# power-v5v5.net
KiCad netlist of a schematic drawn in Altium Designer
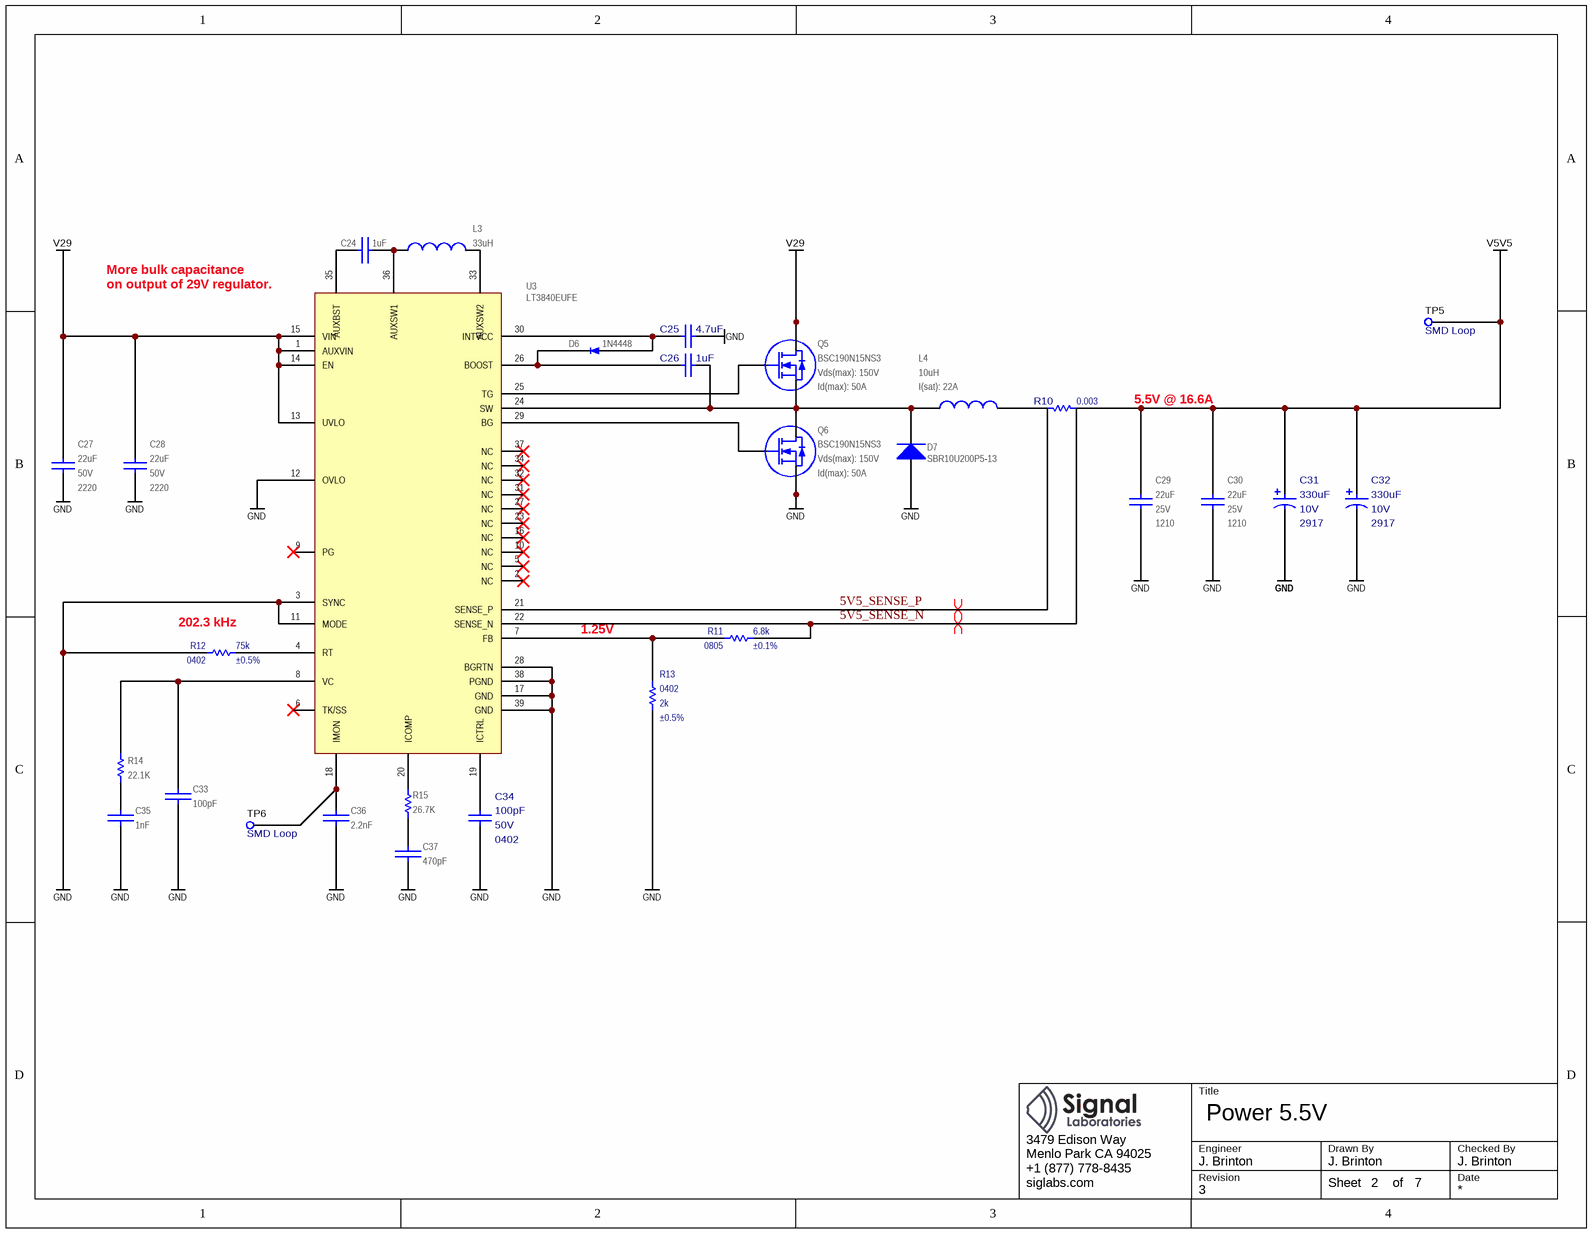
[diagram p0: power-v5v5.SchDoc]

(export (version "E")
  (design (tool "Eeschema 10.0.6"))
  (components
    (comp (ref "C24")
      (value "1uF")
      (footprint "CAPC100X50X55L25N")
      (description "Ceramic Capacitor 1uF ±10% 10V X5R 0402")
      (fields (field (name "MANUFACTURER") "Murata") (field (name "TOLERANCE") "±10%"))
      (libsource (lib "*") (part "CAP"))
    )
    (comp (ref "C25")
      (value "4.7uF")
      (footprint "CAPC160X80X90L20NA")
      (description "Ceramic Capacitor 4.7uF ±10% 25V X5R 0603")
      (fields (field (name "MANUFACTURER") "Samsung") (field (name "TOLERANCE") "±10%"))
      (libsource (lib "capacitors") (part "CAP"))
    )
    (comp (ref "C26")
      (value "1uF")
      (footprint "CAPC100X50X55L25N")
      (description "Ceramic Capacitor 1uF ±10% 10V X5R 0402")
      (fields (field (name "MANUFACTURER") "Murata") (field (name "TOLERANCE") "±10%"))
      (libsource (lib "capacitors") (part "CAP"))
    )
    (comp (ref "C27")
      (value "22uF")
      (footprint "CAPC600X500X500L160N")
      (description "Ceramic Capacitor 22uF ±20% 50V X7S Stacked")
      (fields
        (field (name "MANUFACTURER") "TDK")
        (field (name "TOLERANCE") "±20%")
        (field (name "VOLTAGE") "50V")
        (field (name "PACKAGE") "2220")
      )
      (libsource (lib "generic") (part "CAP"))
    )
    (comp (ref "C28")
      (value "22uF")
      (footprint "CAPC600X500X500L160N")
      (description "Ceramic Capacitor 22uF ±20% 50V X7S Stacked")
      (fields
        (field (name "MANUFACTURER") "TDK")
        (field (name "TOLERANCE") "±20%")
        (field (name "VOLTAGE") "50V")
        (field (name "PACKAGE") "2220")
      )
      (libsource (lib "generic") (part "CAP"))
    )
    (comp (ref "C29")
      (value "22uF")
      (footprint "CAPC320X250X270L50N")
      (description "Ceramic Capacitor 22uF ±10% 25V X7R 1210")
      (fields
        (field (name "MANUFACTURER") "Murata")
        (field (name "TOLERANCE") "±10%")
        (field (name "VOLTAGE") "25V")
        (field (name "PACKAGE") "1210")
      )
      (libsource (lib "generic") (part "CAP"))
    )
    (comp (ref "C30")
      (value "22uF")
      (footprint "CAPC320X250X270L50N")
      (description "Ceramic Capacitor 22uF ±10% 25V X7R 1210")
      (fields
        (field (name "MANUFACTURER") "Murata")
        (field (name "TOLERANCE") "±10%")
        (field (name "VOLTAGE") "25V")
        (field (name "PACKAGE") "1210")
      )
      (libsource (lib "generic") (part "CAP"))
    )
    (comp (ref "C31")
      (value "330uF")
      (footprint "CAPPM730X435X310L135X240N")
      (description "Tantalum Capacitor 330uF ±10% 10V 2917")
      (fields
        (field (name "MANUFACTURER") "AVX")
        (field (name "TOLERANCE") "±10%")
        (field (name "PACKAGE") "2917")
        (field (name "VOLTAGE") "10V")
      )
      (libsource (lib "avx") (part "CAP_POL"))
    )
    (comp (ref "C32")
      (value "330uF")
      (footprint "CAPPM730X435X310L135X240N")
      (description "Tantalum Capacitor 330uF ±10% 10V 2917")
      (fields
        (field (name "MANUFACTURER") "AVX")
        (field (name "TOLERANCE") "±10%")
        (field (name "PACKAGE") "2917")
        (field (name "VOLTAGE") "10V")
      )
      (libsource (lib "avx") (part "CAP_POL"))
    )
    (comp (ref "C33")
      (value "100pF")
      (footprint "CAPC100X50X55L25N")
      (description "Ceramic Capacitor 100pF ±1% 50V NP0 0402")
      (fields (field (name "MANUFACTURER") "Murata") (field (name "VOLTAGE") "50V"))
      (libsource (lib "*") (part "CAP"))
    )
    (comp (ref "C34")
      (value "100pF")
      (footprint "generic:CAPC100X50X55L25N")
      (description "Ceramic Capacitor 100pF ±10% 50V C0G 0402")
      (fields
        (field (name "MANUFACTURER") "Vishay")
        (field (name "TOLERANCE") "±10%")
        (field (name "PACKAGE") "0402")
        (field (name "VOLTAGE") "50V")
      )
      (libsource (lib "capacitors") (part "CAP"))
    )
    (comp (ref "C35")
      (value "1nF")
      (footprint "CAPC100X50X55L25N")
      (description "Ceramic Capacitor 1nF ±5% 50V NP0 0402")
      (fields (field (name "MANUFACTURER") "Murata") (field (name "VOLTAGE") "50V"))
      (libsource (lib "*") (part "CAP"))
    )
    (comp (ref "C36")
      (value "2.2nF")
      (footprint "CAPC100X50X55L25N")
      (description "Ceramic Capacitor 2.2nF ±5% 25V NP0 0402")
      (fields (field (name "MANUFACTURER") "Kemet") (field (name "TOLERANCE") "±5%"))
      (libsource (lib "*") (part "CAP"))
    )
    (comp (ref "C37")
      (value "470pF")
      (footprint "CAPC100X50X55L25N")
      (description "Ceramic Capacitor 470pF ±5% 50V X7R 0402")
      (fields (field (name "MANUFACTURER") "Murata") (field (name "VOLTAGE") "50V"))
      (libsource (lib "*") (part "CAP"))
    )
    (comp (ref "D6")
      (value "1N4448HWS-7-F")
      (footprint "diodes_inc:SOD323")
      (description "Schottky Diode 80V 250mA SOD323")
      (fields (field (name "MANUFACTURER") "Diodes Inc") (field (name "ALTERNATIVE P/N") "1N4448"))
      (libsource (lib "diodes_inc") (part "1N4448HWS-7-F"))
    )
    (comp (ref "D7")
      (value "SBR10U200P5-13")
      (footprint "DIODES_POWERDI5")
      (description "Schottky Diode 200V 10A SMD")
      (fields (field (name "MANUFACTURER") "Diodes Inc"))
      (libsource (lib "diodes_inc") (part "PDS5100H"))
    )
    (comp (ref "L3")
      (value "33uH")
      (footprint "coilcraft:ME3220")
      (description "Inductor 33uH ±10% 500mA SMD")
      (fields (field (name "MANUFACTURER") "Coilcraft") (field (name "TOLERANCE") "±10%"))
      (libsource (lib "CamBoard_Pico_70.19K") (part "COIL"))
    )
    (comp (ref "L4")
      (value "10uH")
      (footprint "HCM1A1707")
      (description "Inductor 10uH, 22A(sat), SMD")
      (fields
        (field (name "MANUFACTURER") "Pulse Electronics Power")
        (field (name "I(SAT)") "22A")
        (field (name "Comment") "PA4344.103ANLT")
      )
      (libsource (lib "CamBoard_Pico_70.19K") (part "COIL"))
    )
    (comp (ref "Q5")
      (value "BSC190N15NS3")
      (footprint "TDSON-8")
      (description "MOSFET N-Channel Enhancement Mode")
      (fields
        (field (name "MANUFACTURER") "Infineon")
        (field (name "VDS(MAX)") "150V")
        (field (name "ID(MAX)") "50A")
      )
      (libsource (lib "infinion") (part "BSC190N15NS3"))
    )
    (comp (ref "Q6")
      (value "BSC190N15NS3")
      (footprint "TDSON-8")
      (description "MOSFET N-Channel Enhancement Mode")
      (fields
        (field (name "MANUFACTURER") "Infineon")
        (field (name "VDS(MAX)") "150V")
        (field (name "ID(MAX)") "50A")
      )
      (libsource (lib "infinion") (part "BSC190N15NS3"))
    )
    (comp (ref "R10")
      (value "0.003")
      (footprint "susumu:KRL3216T4")
      (description "Current Sense Resistor 3 mOhms +/-1% SMD 4-Terminal")
      (fields (field (name "TOLERANCE") "±1%") (field (name "MANUFACTURER") "Susumu"))
      (libsource (lib "susumu") (part "KRL3216T4A-M-R009-F"))
    )
    (comp (ref "R11")
      (value "6.8k")
      (footprint "RESC2012X70N")
      (description "Thin Film Resistor 6.8k +/-0.1% SMD 0805")
      (fields
        (field (name "TOLERANCE") "±0.1%")
        (field (name "MANUFACTURER") "Susumu")
        (field (name "PACKAGE") "0805")
        (field (name "Comment") "RG2012P-682-B-T5")
      )
      (libsource (lib "generic") (part "RES"))
    )
    (comp (ref "R12")
      (value "75k")
      (footprint "RESC1005X40N")
      (description "Thin Film Resistor 75k +/-0.5% SMD 0402")
      (fields
        (field (name "TOLERANCE") "±0.5%")
        (field (name "MANUFACTURER") "Susumu")
        (field (name "PACKAGE") "0402")
        (field (name "Comment") "RR0510P-753-D")
      )
      (libsource (lib "generic") (part "RES"))
    )
    (comp (ref "R13")
      (value "2k")
      (footprint "RESC1005X40N")
      (description "Thin Film Resistor 2k +/-0.5% SMD 0402")
      (fields
        (field (name "TOLERANCE") "±0.5%")
        (field (name "MANUFACTURER") "Susumu")
        (field (name "PACKAGE") "0402")
        (field (name "Comment") "RR0510P-202-D")
      )
      (libsource (lib "generic") (part "RES"))
    )
    (comp (ref "R14")
      (value "22.1K")
      (footprint "generic:RESC1005X40N")
      (description "Thick Film Resistor 22.1k ±1% 0402")
      (fields (field (name "MANUFACTURER") "Panasonic") (field (name "TOLERANCE") "±1%"))
      (libsource (lib "Graviton") (part "RES 0402"))
    )
    (comp (ref "R15")
      (value "26.7K")
      (footprint "generic:RESC1005X40N")
      (description "Thick Film Resistor 26.7k ±1% 0402")
      (fields (field (name "MANUFACTURER") "Panasonic") (field (name "TOLERANCE") "±1%"))
      (libsource (lib "Graviton") (part "RES 0402"))
    )
    (comp (ref "TP5")
      (value "5015")
      (footprint "keystone:5015")
      (description "Test Point SMD")
      (fields (field (name "MANUFACTURER") "Keystone") (field (name "NOTES") "SMD Loop"))
      (libsource (lib "generic") (part "TEST_POINT_SMD_50"))
    )
    (comp (ref "TP6")
      (value "5015")
      (footprint "keystone:5015")
      (description "Test Point SMD")
      (fields (field (name "MANUFACTURER") "Keystone") (field (name "NOTES") "SMD Loop"))
      (libsource (lib "generic") (part "TEST_POINT_SMD_50"))
    )
    (comp (ref "U3")
      (value "LT3840EUFE")
      (footprint "linear:QFN39P40_600X400X80L40X20T465X265N")
      (description "Synchronous Regulator Controller")
      (fields (field (name "MANUFACTURER") "Linear Technology"))
      (libsource (lib "linear") (part "LT3840EUFE"))
    )
  )
  (nets
    (net (code "1") (name "/5V5_SENSE_N") (class "Default")
      (node (ref "R10") (pin "4") (pinfunction "4_4") (pintype "passive"))
      (node (ref "R11") (pin "1") (pinfunction "1_1") (pintype "passive"))
      (node (ref "U3") (pin "22") (pinfunction "SENSE_N_22") (pintype "passive"))
    )
    (net (code "2") (name "/5V5_SENSE_P") (class "Default")
      (node (ref "R10") (pin "3") (pinfunction "3_3") (pintype "passive"))
      (node (ref "U3") (pin "21") (pinfunction "SENSE_P_21") (pintype "passive"))
    )
    (net (code "3") (name "GND") (class "Default")
      (node (ref "C25") (pin "2") (pinfunction "2_2") (pintype "passive"))
      (node (ref "C27") (pin "1") (pinfunction "1_1") (pintype "passive"))
      (node (ref "C28") (pin "1") (pinfunction "1_1") (pintype "passive"))
      (node (ref "C29") (pin "1") (pinfunction "1_1") (pintype "passive"))
      (node (ref "C30") (pin "1") (pinfunction "1_1") (pintype "passive"))
      (node (ref "C31") (pin "2") (pinfunction "2_2") (pintype "passive"))
      (node (ref "C32") (pin "2") (pinfunction "2_2") (pintype "passive"))
      (node (ref "C33") (pin "1") (pinfunction "1_1") (pintype "passive"))
      (node (ref "C34") (pin "2") (pinfunction "2_2") (pintype "passive"))
      (node (ref "C35") (pin "2") (pinfunction "2_2") (pintype "passive"))
      (node (ref "C36") (pin "2") (pinfunction "2_2") (pintype "passive"))
      (node (ref "C37") (pin "1") (pinfunction "1_1") (pintype "passive"))
      (node (ref "D7") (pin "A") (pinfunction "A_A") (pintype "power_in"))
      (node (ref "Q6") (pin "1") (pinfunction "S_1") (pintype "passive"))
      (node (ref "Q6") (pin "2") (pinfunction "S_2") (pintype "passive"))
      (node (ref "Q6") (pin "3") (pinfunction "S_3") (pintype "passive"))
      (node (ref "R12") (pin "2") (pinfunction "2_2") (pintype "passive"))
      (node (ref "R13") (pin "1") (pinfunction "1_1") (pintype "passive"))
      (node (ref "U3") (pin "11") (pinfunction "MODE_11") (pintype "passive"))
      (node (ref "U3") (pin "12") (pinfunction "OVLO_12") (pintype "passive"))
      (node (ref "U3") (pin "17") (pinfunction "GND_17") (pintype "passive"))
      (node (ref "U3") (pin "28") (pinfunction "BGRTN_28") (pintype "passive"))
      (node (ref "U3") (pin "3") (pinfunction "SYNC_3") (pintype "passive"))
      (node (ref "U3") (pin "38") (pinfunction "PGND_38") (pintype "passive"))
      (node (ref "U3") (pin "39") (pinfunction "GND_39") (pintype "passive"))
    )
    (net (code "4") (name "Net-(C35-Pad1)") (class "Default")
      (node (ref "C35") (pin "1") (pinfunction "1_1") (pintype "passive"))
      (node (ref "R14") (pin "1") (pinfunction "1_1") (pintype "passive"))
    )
    (net (code "5") (name "Net-(C37-Pad2)") (class "Default")
      (node (ref "C37") (pin "2") (pinfunction "2_2") (pintype "passive"))
      (node (ref "R15") (pin "2") (pinfunction "2_2") (pintype "passive"))
    )
    (net (code "6") (name "Net-(L4-Pad2)") (class "Default")
      (node (ref "L4") (pin "2") (pinfunction "2_2") (pintype "passive"))
      (node (ref "R10") (pin "1") (pinfunction "1_1") (pintype "passive"))
    )
    (net (code "7") (name "Net-(Q5-G)") (class "Default")
      (node (ref "Q5") (pin "4") (pinfunction "G_4") (pintype "passive"))
      (node (ref "U3") (pin "25") (pinfunction "TG_25") (pintype "passive"))
    )
    (net (code "8") (name "Net-(Q6-G)") (class "Default")
      (node (ref "Q6") (pin "4") (pinfunction "G_4") (pintype "passive"))
      (node (ref "U3") (pin "29") (pinfunction "BG_29") (pintype "passive"))
    )
    (net (code "9") (name "Net-(U3-AUXBST)") (class "Default")
      (node (ref "C24") (pin "2") (pinfunction "2_2") (pintype "passive"))
      (node (ref "U3") (pin "35") (pinfunction "AUXBST_35") (pintype "passive"))
    )
    (net (code "10") (name "Net-(U3-AUXSW1)") (class "Default")
      (node (ref "C24") (pin "1") (pinfunction "1_1") (pintype "passive"))
      (node (ref "L3") (pin "1") (pinfunction "1_1") (pintype "passive"))
      (node (ref "U3") (pin "36") (pinfunction "AUXSW1_36") (pintype "passive"))
    )
    (net (code "11") (name "Net-(U3-AUXSW2)") (class "Default")
      (node (ref "L3") (pin "2") (pinfunction "2_2") (pintype "passive"))
      (node (ref "U3") (pin "33") (pinfunction "AUXSW2_33") (pintype "passive"))
    )
    (net (code "12") (name "Net-(U3-BOOST)") (class "Default")
      (node (ref "C26") (pin "1") (pinfunction "1_1") (pintype "passive"))
      (node (ref "D6") (pin "K") (pinfunction "K_K") (pintype "passive"))
      (node (ref "U3") (pin "26") (pinfunction "BOOST_26") (pintype "passive"))
    )
    (net (code "13") (name "Net-(U3-FB)") (class "Default")
      (node (ref "R11") (pin "2") (pinfunction "2_2") (pintype "passive"))
      (node (ref "R13") (pin "2") (pinfunction "2_2") (pintype "passive"))
      (node (ref "U3") (pin "7") (pinfunction "FB_7") (pintype "passive"))
    )
    (net (code "14") (name "Net-(U3-ICOMP)") (class "Default")
      (node (ref "R15") (pin "1") (pinfunction "1_1") (pintype "passive"))
      (node (ref "U3") (pin "20") (pinfunction "ICOMP_20") (pintype "passive"))
    )
    (net (code "15") (name "Net-(U3-ICTRL)") (class "Default")
      (node (ref "C34") (pin "1") (pinfunction "1_1") (pintype "passive"))
      (node (ref "U3") (pin "19") (pinfunction "ICTRL_19") (pintype "passive"))
    )
    (net (code "16") (name "Net-(U3-IMON)") (class "Default")
      (node (ref "C36") (pin "1") (pinfunction "1_1") (pintype "passive"))
      (node (ref "TP6") (pin "1") (pinfunction "1_1") (pintype "passive"))
      (node (ref "U3") (pin "18") (pinfunction "IMON_18") (pintype "passive"))
    )
    (net (code "17") (name "Net-(U3-INTVCC)") (class "Default")
      (node (ref "C25") (pin "1") (pinfunction "1_1") (pintype "passive"))
      (node (ref "D6") (pin "A") (pinfunction "A_A") (pintype "passive"))
      (node (ref "U3") (pin "30") (pinfunction "INTVCC_30") (pintype "passive"))
    )
    (net (code "18") (name "Net-(U3-RT)") (class "Default")
      (node (ref "R12") (pin "1") (pinfunction "1_1") (pintype "passive"))
      (node (ref "U3") (pin "4") (pinfunction "RT_4") (pintype "passive"))
    )
    (net (code "19") (name "Net-(U3-SW)") (class "Default")
      (node (ref "C26") (pin "2") (pinfunction "2_2") (pintype "passive"))
      (node (ref "D7") (pin "K") (pinfunction "K_K") (pintype "passive"))
      (node (ref "L4") (pin "1") (pinfunction "1_1") (pintype "passive"))
      (node (ref "Q5") (pin "1") (pinfunction "S_1") (pintype "passive"))
      (node (ref "Q5") (pin "2") (pinfunction "S_2") (pintype "passive"))
      (node (ref "Q5") (pin "3") (pinfunction "S_3") (pintype "passive"))
      (node (ref "Q6") (pin "5") (pinfunction "D_5") (pintype "passive"))
      (node (ref "Q6") (pin "6") (pinfunction "D_6") (pintype "passive"))
      (node (ref "Q6") (pin "7") (pinfunction "D_7") (pintype "passive"))
      (node (ref "Q6") (pin "8") (pinfunction "D_8") (pintype "passive"))
      (node (ref "Q6") (pin "9") (pinfunction "D_9") (pintype "passive"))
      (node (ref "U3") (pin "24") (pinfunction "SW_24") (pintype "passive"))
    )
    (net (code "20") (name "Net-(U3-VC)") (class "Default")
      (node (ref "C33") (pin "2") (pinfunction "2_2") (pintype "passive"))
      (node (ref "R14") (pin "2") (pinfunction "2_2") (pintype "passive"))
      (node (ref "U3") (pin "8") (pinfunction "VC_8") (pintype "passive"))
    )
    (net (code "21") (name "V5V5") (class "Default")
      (node (ref "C29") (pin "2") (pinfunction "2_2") (pintype "passive"))
      (node (ref "C30") (pin "2") (pinfunction "2_2") (pintype "passive"))
      (node (ref "C31") (pin "1") (pinfunction "1_1") (pintype "passive"))
      (node (ref "C32") (pin "1") (pinfunction "1_1") (pintype "passive"))
      (node (ref "R10") (pin "2") (pinfunction "2_2") (pintype "passive"))
      (node (ref "TP5") (pin "1") (pinfunction "1_1") (pintype "passive"))
    )
    (net (code "22") (name "V29") (class "Default")
      (node (ref "C27") (pin "2") (pinfunction "2_2") (pintype "passive"))
      (node (ref "C28") (pin "2") (pinfunction "2_2") (pintype "passive"))
      (node (ref "Q5") (pin "5") (pinfunction "D_5") (pintype "passive"))
      (node (ref "Q5") (pin "6") (pinfunction "D_6") (pintype "passive"))
      (node (ref "Q5") (pin "7") (pinfunction "D_7") (pintype "passive"))
      (node (ref "Q5") (pin "8") (pinfunction "D_8") (pintype "passive"))
      (node (ref "Q5") (pin "9") (pinfunction "D_9") (pintype "passive"))
      (node (ref "U3") (pin "1") (pinfunction "AUXVIN_1") (pintype "passive"))
      (node (ref "U3") (pin "13") (pinfunction "UVLO_13") (pintype "passive"))
      (node (ref "U3") (pin "14") (pinfunction "EN_14") (pintype "passive"))
      (node (ref "U3") (pin "15") (pinfunction "VIN_15") (pintype "passive"))
    )
    (net (code "23") (name "unconnected-(U3-NC-Pad2)") (class "Default")
      (node (ref "U3") (pin "2") (pinfunction "NC_2") (pintype "passive+no_connect"))
    )
    (net (code "24") (name "unconnected-(U3-NC-Pad5)") (class "Default")
      (node (ref "U3") (pin "5") (pinfunction "NC_5") (pintype "passive+no_connect"))
    )
    (net (code "25") (name "unconnected-(U3-NC-Pad10)") (class "Default")
      (node (ref "U3") (pin "10") (pinfunction "NC_10") (pintype "passive+no_connect"))
    )
    (net (code "26") (name "unconnected-(U3-NC-Pad16)") (class "Default")
      (node (ref "U3") (pin "16") (pinfunction "NC_16") (pintype "passive+no_connect"))
    )
    (net (code "27") (name "unconnected-(U3-NC-Pad23)") (class "Default")
      (node (ref "U3") (pin "23") (pinfunction "NC_23") (pintype "passive+no_connect"))
    )
    (net (code "28") (name "unconnected-(U3-NC-Pad27)") (class "Default")
      (node (ref "U3") (pin "27") (pinfunction "NC_27") (pintype "passive+no_connect"))
    )
    (net (code "29") (name "unconnected-(U3-NC-Pad31)") (class "Default")
      (node (ref "U3") (pin "31") (pinfunction "NC_31") (pintype "passive+no_connect"))
    )
    (net (code "30") (name "unconnected-(U3-NC-Pad32)") (class "Default")
      (node (ref "U3") (pin "32") (pinfunction "NC_32") (pintype "passive+no_connect"))
    )
    (net (code "31") (name "unconnected-(U3-NC-Pad34)") (class "Default")
      (node (ref "U3") (pin "34") (pinfunction "NC_34") (pintype "passive+no_connect"))
    )
    (net (code "32") (name "unconnected-(U3-NC-Pad37)") (class "Default")
      (node (ref "U3") (pin "37") (pinfunction "NC_37") (pintype "passive+no_connect"))
    )
    (net (code "33") (name "unconnected-(U3-PG-Pad9)") (class "Default")
      (node (ref "U3") (pin "9") (pinfunction "PG_9") (pintype "passive+no_connect"))
    )
    (net (code "34") (name "unconnected-(U3-TK{slash}SS-Pad6)") (class "Default")
      (node (ref "U3") (pin "6") (pinfunction "TK/SS_6") (pintype "passive+no_connect"))
    )
  )
)
